# Sheet1.net
KiCad netlist of a schematic drawn in Altium Designer
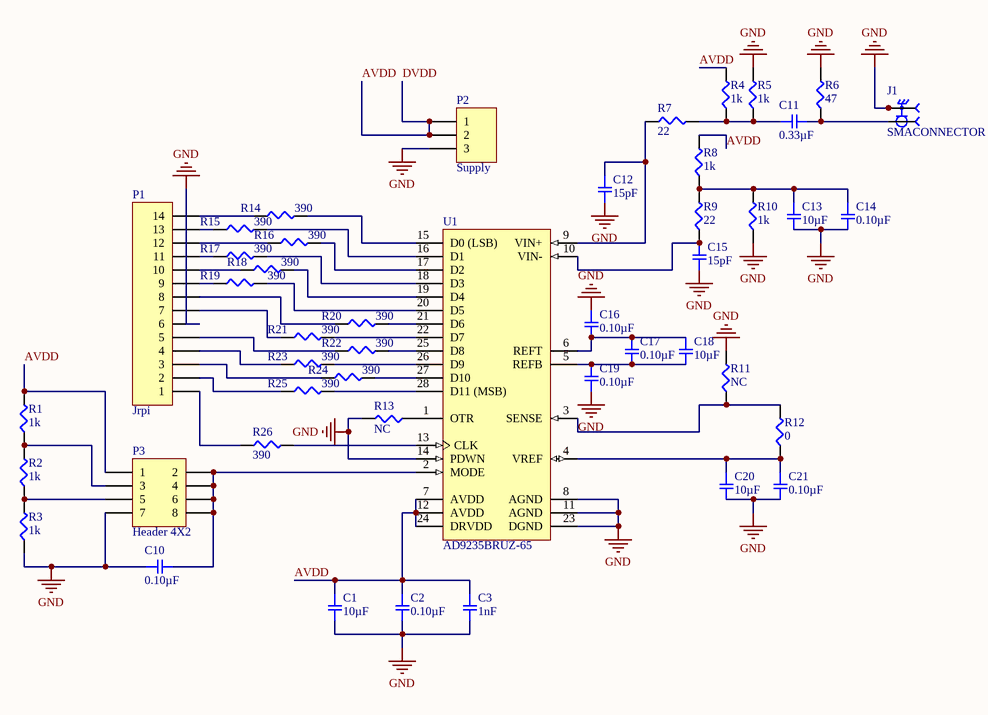
[diagram p0: Sheet1.SchDoc]

(export (version "E")
  (design (tool "Eeschema 10.0.6"))
  (components
    (comp (ref "C1")
      (value "10µF")
      (footprint "SMD-0603C")
      (description "CAP CER 10UF 6.3V X5R 0603")
      (fields
        (field (name "DIGI-KEY PART NUMBER") "490-10467-1-ND")
        (field (name "PART NUMBER") "GRM185R60J106ME15D")
      )
      (libsource (lib "capacitor_murata_0603") (part "GRM185R60J106ME15D"))
    )
    (comp (ref "C2")
      (value "0.10µF")
      (footprint "SMD-0603C")
      (description "CAP CER 0.1UF 16V X7R 0603")
      (fields
        (field (name "DIGI-KEY PART NUMBER") "490-5796-1-ND")
        (field (name "PART NUMBER") "GCJ188R71C104KA01D")
      )
      (libsource (lib "capacitor_murata_0603") (part "GCJ188R71C104KA01D"))
    )
    (comp (ref "C3")
      (value "1nF")
      (footprint "SMD-0603C")
      (description "CAP CER 1000PF 50V X7R 0603")
      (fields
        (field (name "DIGI-KEY PART NUMBER") "490-5768-1-ND")
        (field (name "PART NUMBER") "GCJ188R71H102KA01D")
      )
      (libsource (lib "capacitor_murata_0603") (part "GCJ188R71H102KA01D"))
    )
    (comp (ref "C10")
      (value "0.10µF")
      (footprint "SMD-0603C")
      (description "CAP CER 0.1UF 16V X7R 0603")
      (fields
        (field (name "DIGI-KEY PART NUMBER") "490-5796-1-ND")
        (field (name "PART NUMBER") "GCJ188R71C104KA01D")
      )
      (libsource (lib "capacitor_murata_0603") (part "GCJ188R71C104KA01D"))
    )
    (comp (ref "C11")
      (value "0.33µF")
      (footprint "SMD-0603C")
      (description "CAP CER 0.33UF 16V X7R 0603")
      (fields
        (field (name "DIGI-KEY PART NUMBER") "490-6050-1-ND")
        (field (name "PART NUMBER") "GCM188R71C334KA37D")
      )
      (libsource (lib "capacitor_murata_0603") (part "GCM188R71C334KA37D"))
    )
    (comp (ref "C12")
      (value "15pF")
      (footprint "SMD-0603C")
      (description "CAP CER 15PF 50V NP0 0603")
      (fields
        (field (name "DIGI-KEY PART NUMBER") "490-4957-1-ND")
        (field (name "PART NUMBER") "GCM1885C1H150JA16D")
      )
      (libsource (lib "capacitor_murata_0603") (part "GCM1885C1H150JA16D"))
    )
    (comp (ref "C13")
      (value "10µF")
      (footprint "SMD-0603C")
      (description "CAP CER 10UF 6.3V X5R 0603")
      (fields
        (field (name "DIGI-KEY PART NUMBER") "490-10467-1-ND")
        (field (name "PART NUMBER") "GRM185R60J106ME15D")
      )
      (libsource (lib "capacitor_murata_0603") (part "GRM185R60J106ME15D"))
    )
    (comp (ref "C14")
      (value "0.10µF")
      (footprint "SMD-0603C")
      (description "CAP CER 0.1UF 16V X7R 0603")
      (fields
        (field (name "DIGI-KEY PART NUMBER") "490-5796-1-ND")
        (field (name "PART NUMBER") "GCJ188R71C104KA01D")
      )
      (libsource (lib "capacitor_murata_0603") (part "GCJ188R71C104KA01D"))
    )
    (comp (ref "C15")
      (value "15pF")
      (footprint "SMD-0603C")
      (description "CAP CER 15PF 50V NP0 0603")
      (fields
        (field (name "DIGI-KEY PART NUMBER") "490-4957-1-ND")
        (field (name "PART NUMBER") "GCM1885C1H150JA16D")
      )
      (libsource (lib "capacitor_murata_0603") (part "GCM1885C1H150JA16D"))
    )
    (comp (ref "C16")
      (value "0.10µF")
      (footprint "SMD-0603C")
      (description "CAP CER 0.1UF 16V X7R 0603")
      (fields
        (field (name "DIGI-KEY PART NUMBER") "490-5796-1-ND")
        (field (name "PART NUMBER") "GCJ188R71C104KA01D")
      )
      (libsource (lib "capacitor_murata_0603") (part "GCJ188R71C104KA01D"))
    )
    (comp (ref "C17")
      (value "0.10µF")
      (footprint "SMD-0603C")
      (description "CAP CER 0.1UF 16V X7R 0603")
      (fields
        (field (name "DIGI-KEY PART NUMBER") "490-5796-1-ND")
        (field (name "PART NUMBER") "GCJ188R71C104KA01D")
      )
      (libsource (lib "capacitor_murata_0603") (part "GCJ188R71C104KA01D"))
    )
    (comp (ref "C18")
      (value "10µF")
      (footprint "SMD-0603C")
      (description "CAP CER 10UF 6.3V X5R 0603")
      (fields
        (field (name "DIGI-KEY PART NUMBER") "490-10467-1-ND")
        (field (name "PART NUMBER") "GRM185R60J106ME15D")
      )
      (libsource (lib "capacitor_murata_0603") (part "GRM185R60J106ME15D"))
    )
    (comp (ref "C19")
      (value "0.10µF")
      (footprint "SMD-0603C")
      (description "CAP CER 0.1UF 16V X7R 0603")
      (fields
        (field (name "DIGI-KEY PART NUMBER") "490-5796-1-ND")
        (field (name "PART NUMBER") "GCJ188R71C104KA01D")
      )
      (libsource (lib "capacitor_murata_0603") (part "GCJ188R71C104KA01D"))
    )
    (comp (ref "C20")
      (value "10µF")
      (footprint "SMD-0603C")
      (description "CAP CER 10UF 6.3V X5R 0603")
      (fields
        (field (name "DIGI-KEY PART NUMBER") "490-10467-1-ND")
        (field (name "PART NUMBER") "GRM185R60J106ME15D")
      )
      (libsource (lib "capacitor_murata_0603") (part "GRM185R60J106ME15D"))
    )
    (comp (ref "C21")
      (value "0.10µF")
      (footprint "SMD-0603C")
      (description "CAP CER 0.1UF 16V X7R 0603")
      (fields
        (field (name "DIGI-KEY PART NUMBER") "490-5796-1-ND")
        (field (name "PART NUMBER") "GCJ188R71C104KA01D")
      )
      (libsource (lib "capacitor_murata_0603") (part "GCJ188R71C104KA01D"))
    )
    (comp (ref "J1")
      (value "SMACONNECTOR")
      (footprint "LPRS_SMACONNECTOR")
      (description "SMA female RF coaxial connector for SMA male RF antennas.")
      (libsource (lib "SMACONNECTOR") (part "SMACONNECTOR"))
    )
    (comp (ref "P1")
      (value "Jrpi")
      (footprint "HDR1X14")
      (description "Header, 14-Pin")
      (fields (field (name "PUBLISHER") "Altium Limited"))
      (libsource (lib "Miscellaneous Connectors") (part "Header 14"))
    )
    (comp (ref "P2")
      (value "Supply")
      (footprint "HDR1X3")
      (description "Header, 3-Pin")
      (fields (field (name "PUBLISHER") "Altium Limited"))
      (libsource (lib "Miscellaneous Connectors") (part "Header 3"))
    )
    (comp (ref "P3")
      (value "Header 4X2")
      (footprint "HDR2X4")
      (description "Header, 4-Pin, Dual row")
      (fields (field (name "PUBLISHER") "Altium Limited"))
      (libsource (lib "Miscellaneous Connectors") (part "Header 4X2"))
    )
    (comp (ref "R1")
      (value "1k")
      (footprint "SMD-0603-RES")
      (description "RES SMD 1K OHM 1% 1/10W 0603")
      (fields
        (field (name "PART NUMBER") "ERJ-3EKF1001V")
        (field (name "DIGI-KEY PART NUMBER") "P1.00KHCT-ND")
      )
      (libsource (lib "Panasonic_ERJ_0603") (part "ERJ-3EKF1001V"))
    )
    (comp (ref "R2")
      (value "1k")
      (footprint "SMD-0603-RES")
      (description "RES SMD 1K OHM 1% 1/10W 0603")
      (fields
        (field (name "PART NUMBER") "ERJ-3EKF1001V")
        (field (name "DIGI-KEY PART NUMBER") "P1.00KHCT-ND")
      )
      (libsource (lib "Panasonic_ERJ_0603") (part "ERJ-3EKF1001V"))
    )
    (comp (ref "R3")
      (value "1k")
      (footprint "SMD-0603-RES")
      (description "RES SMD 1K OHM 1% 1/10W 0603")
      (fields
        (field (name "PART NUMBER") "ERJ-3EKF1001V")
        (field (name "DIGI-KEY PART NUMBER") "P1.00KHCT-ND")
      )
      (libsource (lib "Panasonic_ERJ_0603") (part "ERJ-3EKF1001V"))
    )
    (comp (ref "R4")
      (value "1k")
      (footprint "SMD-0603-RES")
      (description "RES SMD 1K OHM 1% 1/10W 0603")
      (fields
        (field (name "PART NUMBER") "ERJ-3EKF1001V")
        (field (name "DIGI-KEY PART NUMBER") "P1.00KHCT-ND")
      )
      (libsource (lib "Panasonic_ERJ_0603") (part "ERJ-3EKF1001V"))
    )
    (comp (ref "R5")
      (value "1k")
      (footprint "SMD-0603-RES")
      (description "RES SMD 1K OHM 1% 1/10W 0603")
      (fields
        (field (name "PART NUMBER") "ERJ-3EKF1001V")
        (field (name "DIGI-KEY PART NUMBER") "P1.00KHCT-ND")
      )
      (libsource (lib "Panasonic_ERJ_0603") (part "ERJ-3EKF1001V"))
    )
    (comp (ref "R6")
      (value "47")
      (footprint "SMD-0603-RES")
      (description "RES SMD 47 OHM 1% 1/4W 0603")
      (fields
        (field (name "PART NUMBER") "ERJ-PA3F47R0V")
        (field (name "DIGI-KEY PART NUMBER") "P47.00BYCT-ND")
      )
      (libsource (lib "Panasonic_ERJ_0603") (part "ERJ-PA3F47R0V"))
    )
    (comp (ref "R7")
      (value "22")
      (footprint "SMD-0603-RES")
      (description "RES SMD 22 OHM 5% 1/10W 0603")
      (fields (field (name "PART NUMBER") "ERJ-3GEYJ220V") (field (name "DIGI-KEY PART NUMBER") "P22GCT-ND"))
      (libsource (lib "Panasonic_ERJ_0603") (part "ERJ-3GEYJ220V"))
    )
    (comp (ref "R8")
      (value "1k")
      (footprint "SMD-0603-RES")
      (description "RES SMD 1K OHM 1% 1/10W 0603")
      (fields
        (field (name "PART NUMBER") "ERJ-3EKF1001V")
        (field (name "DIGI-KEY PART NUMBER") "P1.00KHCT-ND")
      )
      (libsource (lib "Panasonic_ERJ_0603") (part "ERJ-3EKF1001V"))
    )
    (comp (ref "R9")
      (value "22")
      (footprint "SMD-0603-RES")
      (description "RES SMD 22 OHM 5% 1/10W 0603")
      (fields (field (name "PART NUMBER") "ERJ-3GEYJ220V") (field (name "DIGI-KEY PART NUMBER") "P22GCT-ND"))
      (libsource (lib "Panasonic_ERJ_0603") (part "ERJ-3GEYJ220V"))
    )
    (comp (ref "R10")
      (value "1k")
      (footprint "SMD-0603-RES")
      (description "RES SMD 1K OHM 1% 1/10W 0603")
      (fields
        (field (name "PART NUMBER") "ERJ-3EKF1001V")
        (field (name "DIGI-KEY PART NUMBER") "P1.00KHCT-ND")
      )
      (libsource (lib "Panasonic_ERJ_0603") (part "ERJ-3EKF1001V"))
    )
    (comp (ref "R11")
      (value "NC")
      (footprint "SMD-0603-RES")
      (description "RES SMD 0.02 OHM 1% 1/3W 0603")
      (fields
        (field (name "PART NUMBER") "ERJ-3BWFR020V")
        (field (name "DIGI-KEY PART NUMBER") "P17461CT-ND")
      )
      (libsource (lib "Panasonic_ERJ_0603") (part "ERJ-3BWFR020V"))
    )
    (comp (ref "R12")
      (value "0")
      (footprint "SMD-0603-RES")
      (description "RES SMD 0.02 OHM 1% 1/3W 0603")
      (fields
        (field (name "PART NUMBER") "ERJ-3BWFR020V")
        (field (name "DIGI-KEY PART NUMBER") "P17461CT-ND")
      )
      (libsource (lib "Panasonic_ERJ_0603") (part "ERJ-3BWFR020V"))
    )
    (comp (ref "R13")
      (value "NC")
      (footprint "SMD-0603-RES")
      (description "RES SMD 0.02 OHM 1% 1/3W 0603")
      (fields
        (field (name "PART NUMBER") "ERJ-3BWFR020V")
        (field (name "DIGI-KEY PART NUMBER") "P17461CT-ND")
      )
      (libsource (lib "Panasonic_ERJ_0603") (part "ERJ-3BWFR020V"))
    )
    (comp (ref "R14")
      (value "390")
      (footprint "SMD-0603-RES")
      (description "RES SMD 390 OHM 1% 1/10W 0603")
      (fields (field (name "PART NUMBER") "ERJ-3EKF3900V") (field (name "DIGI-KEY PART NUMBER") "P390HCT-ND"))
      (libsource (lib "Panasonic_ERJ_0603") (part "ERJ-3EKF3900V"))
    )
    (comp (ref "R15")
      (value "390")
      (footprint "SMD-0603-RES")
      (description "RES SMD 390 OHM 1% 1/10W 0603")
      (fields (field (name "PART NUMBER") "ERJ-3EKF3900V") (field (name "DIGI-KEY PART NUMBER") "P390HCT-ND"))
      (libsource (lib "Panasonic_ERJ_0603") (part "ERJ-3EKF3900V"))
    )
    (comp (ref "R16")
      (value "390")
      (footprint "SMD-0603-RES")
      (description "RES SMD 390 OHM 1% 1/10W 0603")
      (fields (field (name "PART NUMBER") "ERJ-3EKF3900V") (field (name "DIGI-KEY PART NUMBER") "P390HCT-ND"))
      (libsource (lib "Panasonic_ERJ_0603") (part "ERJ-3EKF3900V"))
    )
    (comp (ref "R17")
      (value "390")
      (footprint "SMD-0603-RES")
      (description "RES SMD 390 OHM 1% 1/10W 0603")
      (fields (field (name "PART NUMBER") "ERJ-3EKF3900V") (field (name "DIGI-KEY PART NUMBER") "P390HCT-ND"))
      (libsource (lib "Panasonic_ERJ_0603") (part "ERJ-3EKF3900V"))
    )
    (comp (ref "R18")
      (value "390")
      (footprint "SMD-0603-RES")
      (description "RES SMD 390 OHM 1% 1/10W 0603")
      (fields (field (name "PART NUMBER") "ERJ-3EKF3900V") (field (name "DIGI-KEY PART NUMBER") "P390HCT-ND"))
      (libsource (lib "Panasonic_ERJ_0603") (part "ERJ-3EKF3900V"))
    )
    (comp (ref "R19")
      (value "390")
      (footprint "SMD-0603-RES")
      (description "RES SMD 390 OHM 1% 1/10W 0603")
      (fields (field (name "PART NUMBER") "ERJ-3EKF3900V") (field (name "DIGI-KEY PART NUMBER") "P390HCT-ND"))
      (libsource (lib "Panasonic_ERJ_0603") (part "ERJ-3EKF3900V"))
    )
    (comp (ref "R20")
      (value "390")
      (footprint "SMD-0603-RES")
      (description "RES SMD 390 OHM 1% 1/10W 0603")
      (fields (field (name "PART NUMBER") "ERJ-3EKF3900V") (field (name "DIGI-KEY PART NUMBER") "P390HCT-ND"))
      (libsource (lib "Panasonic_ERJ_0603") (part "ERJ-3EKF3900V"))
    )
    (comp (ref "R21")
      (value "390")
      (footprint "SMD-0603-RES")
      (description "RES SMD 390 OHM 1% 1/10W 0603")
      (fields (field (name "PART NUMBER") "ERJ-3EKF3900V") (field (name "DIGI-KEY PART NUMBER") "P390HCT-ND"))
      (libsource (lib "Panasonic_ERJ_0603") (part "ERJ-3EKF3900V"))
    )
    (comp (ref "R22")
      (value "390")
      (footprint "SMD-0603-RES")
      (description "RES SMD 390 OHM 1% 1/10W 0603")
      (fields (field (name "PART NUMBER") "ERJ-3EKF3900V") (field (name "DIGI-KEY PART NUMBER") "P390HCT-ND"))
      (libsource (lib "Panasonic_ERJ_0603") (part "ERJ-3EKF3900V"))
    )
    (comp (ref "R23")
      (value "390")
      (footprint "SMD-0603-RES")
      (description "RES SMD 390 OHM 1% 1/10W 0603")
      (fields (field (name "PART NUMBER") "ERJ-3EKF3900V") (field (name "DIGI-KEY PART NUMBER") "P390HCT-ND"))
      (libsource (lib "Panasonic_ERJ_0603") (part "ERJ-3EKF3900V"))
    )
    (comp (ref "R24")
      (value "390")
      (footprint "SMD-0603-RES")
      (description "RES SMD 390 OHM 1% 1/10W 0603")
      (fields (field (name "PART NUMBER") "ERJ-3EKF3900V") (field (name "DIGI-KEY PART NUMBER") "P390HCT-ND"))
      (libsource (lib "Panasonic_ERJ_0603") (part "ERJ-3EKF3900V"))
    )
    (comp (ref "R25")
      (value "390")
      (footprint "SMD-0603-RES")
      (description "RES SMD 390 OHM 1% 1/10W 0603")
      (fields (field (name "PART NUMBER") "ERJ-3EKF3900V") (field (name "DIGI-KEY PART NUMBER") "P390HCT-ND"))
      (libsource (lib "Panasonic_ERJ_0603") (part "ERJ-3EKF3900V"))
    )
    (comp (ref "R26")
      (value "390")
      (footprint "SMD-0603-RES")
      (description "RES SMD 390 OHM 1% 1/10W 0603")
      (fields (field (name "PART NUMBER") "ERJ-3EKF3900V") (field (name "DIGI-KEY PART NUMBER") "P390HCT-ND"))
      (libsource (lib "Panasonic_ERJ_0603") (part "ERJ-3EKF3900V"))
    )
    (comp (ref "U1")
      (value "AD9235BRUZ-65")
      (footprint "RU-28_M")
      (fields (field (name "GENERIC PART NUMBER") "AD9235-65") (field (name "MANUFACTURER") "Analog Devices"))
      (libsource (lib "Altium Content Vault") (part "ADI-AD9235-65-RU-28"))
    )
  )
  (nets
    (net (code "1") (name "/AVDD") (class "Default")
      (node (ref "C1") (pin "1") (pinfunction "1_1") (pintype "passive"))
      (node (ref "C2") (pin "1") (pinfunction "1_1") (pintype "passive"))
      (node (ref "C3") (pin "1") (pinfunction "1_1") (pintype "passive"))
      (node (ref "P2") (pin "1") (pinfunction "1_1") (pintype "passive"))
      (node (ref "P2") (pin "2") (pinfunction "2_2") (pintype "passive"))
      (node (ref "P3") (pin "1") (pinfunction "1_1") (pintype "passive"))
      (node (ref "R1") (pin "2") (pinfunction "2_2") (pintype "passive"))
      (node (ref "R4") (pin "2") (pinfunction "2_2") (pintype "passive"))
      (node (ref "R8") (pin "2") (pinfunction "2_2") (pintype "passive"))
      (node (ref "U1") (pin "12") (pinfunction "AVDD_12") (pintype "power_in"))
      (node (ref "U1") (pin "24") (pinfunction "DRVDD_24") (pintype "power_in"))
      (node (ref "U1") (pin "7") (pinfunction "AVDD_7") (pintype "power_in"))
    )
    (net (code "2") (name "GND") (class "Default")
      (node (ref "C1") (pin "2") (pinfunction "2_2") (pintype "passive"))
      (node (ref "C10") (pin "1") (pinfunction "1_1") (pintype "passive"))
      (node (ref "C12") (pin "2") (pinfunction "2_2") (pintype "passive"))
      (node (ref "C13") (pin "2") (pinfunction "2_2") (pintype "passive"))
      (node (ref "C14") (pin "2") (pinfunction "2_2") (pintype "passive"))
      (node (ref "C15") (pin "2") (pinfunction "2_2") (pintype "passive"))
      (node (ref "C16") (pin "1") (pinfunction "1_1") (pintype "passive"))
      (node (ref "C19") (pin "2") (pinfunction "2_2") (pintype "passive"))
      (node (ref "C2") (pin "2") (pinfunction "2_2") (pintype "passive"))
      (node (ref "C20") (pin "2") (pinfunction "2_2") (pintype "passive"))
      (node (ref "C21") (pin "2") (pinfunction "2_2") (pintype "passive"))
      (node (ref "C3") (pin "2") (pinfunction "2_2") (pintype "passive"))
      (node (ref "J1") (pin "2") (pinfunction "2_2") (pintype "passive"))
      (node (ref "J1") (pin "3") (pinfunction "2_3") (pintype "passive"))
      (node (ref "J1") (pin "4") (pinfunction "2_4") (pintype "passive"))
      (node (ref "J1") (pin "5") (pinfunction "2_5") (pintype "passive"))
      (node (ref "P1") (pin "6") (pinfunction "6_6") (pintype "passive"))
      (node (ref "P2") (pin "3") (pinfunction "3_3") (pintype "passive"))
      (node (ref "P3") (pin "7") (pinfunction "7_7") (pintype "passive"))
      (node (ref "R10") (pin "1") (pinfunction "1_1") (pintype "passive"))
      (node (ref "R11") (pin "2") (pinfunction "2_2") (pintype "passive"))
      (node (ref "R13") (pin "2") (pinfunction "2_2") (pintype "passive"))
      (node (ref "R3") (pin "1") (pinfunction "1_1") (pintype "passive"))
      (node (ref "R5") (pin "2") (pinfunction "2_2") (pintype "passive"))
      (node (ref "R6") (pin "2") (pinfunction "2_2") (pintype "passive"))
      (node (ref "U1") (pin "11") (pinfunction "AGND_11") (pintype "power_in"))
      (node (ref "U1") (pin "14") (pinfunction "PDWN_14") (pintype "input"))
      (node (ref "U1") (pin "23") (pinfunction "DGND_23") (pintype "power_in"))
      (node (ref "U1") (pin "8") (pinfunction "AGND_8") (pintype "power_in"))
    )
    (net (code "3") (name "Net-(C11-Pad1)") (class "Default")
      (node (ref "C11") (pin "1") (pinfunction "1_1") (pintype "passive"))
      (node (ref "R4") (pin "1") (pinfunction "1_1") (pintype "passive"))
      (node (ref "R5") (pin "1") (pinfunction "1_1") (pintype "passive"))
      (node (ref "R7") (pin "2") (pinfunction "2_2") (pintype "passive"))
    )
    (net (code "4") (name "Net-(C11-Pad2)") (class "Default")
      (node (ref "C11") (pin "2") (pinfunction "2_2") (pintype "passive"))
      (node (ref "J1") (pin "1") (pinfunction "1_1") (pintype "passive"))
      (node (ref "R6") (pin "1") (pinfunction "1_1") (pintype "passive"))
    )
    (net (code "5") (name "Net-(C13-Pad1)") (class "Default")
      (node (ref "C13") (pin "1") (pinfunction "1_1") (pintype "passive"))
      (node (ref "C14") (pin "1") (pinfunction "1_1") (pintype "passive"))
      (node (ref "R10") (pin "2") (pinfunction "2_2") (pintype "passive"))
      (node (ref "R8") (pin "1") (pinfunction "1_1") (pintype "passive"))
      (node (ref "R9") (pin "2") (pinfunction "2_2") (pintype "passive"))
    )
    (net (code "6") (name "Net-(P1-Pad1)") (class "Default")
      (node (ref "P1") (pin "1") (pinfunction "1_1") (pintype "passive"))
      (node (ref "R26") (pin "1") (pinfunction "1_1") (pintype "passive"))
    )
    (net (code "7") (name "Net-(P1-Pad2)") (class "Default")
      (node (ref "P1") (pin "2") (pinfunction "2_2") (pintype "passive"))
      (node (ref "R25") (pin "1") (pinfunction "1_1") (pintype "passive"))
    )
    (net (code "8") (name "Net-(P1-Pad3)") (class "Default")
      (node (ref "P1") (pin "3") (pinfunction "3_3") (pintype "passive"))
      (node (ref "R24") (pin "1") (pinfunction "1_1") (pintype "passive"))
    )
    (net (code "9") (name "Net-(P1-Pad4)") (class "Default")
      (node (ref "P1") (pin "4") (pinfunction "4_4") (pintype "passive"))
      (node (ref "R23") (pin "1") (pinfunction "1_1") (pintype "passive"))
    )
    (net (code "10") (name "Net-(P1-Pad5)") (class "Default")
      (node (ref "P1") (pin "5") (pinfunction "5_5") (pintype "passive"))
      (node (ref "R22") (pin "1") (pinfunction "1_1") (pintype "passive"))
    )
    (net (code "11") (name "Net-(P1-Pad7)") (class "Default")
      (node (ref "P1") (pin "7") (pinfunction "7_7") (pintype "passive"))
      (node (ref "R21") (pin "1") (pinfunction "1_1") (pintype "passive"))
    )
    (net (code "12") (name "Net-(P1-Pad8)") (class "Default")
      (node (ref "P1") (pin "8") (pinfunction "8_8") (pintype "passive"))
      (node (ref "R20") (pin "1") (pinfunction "1_1") (pintype "passive"))
    )
    (net (code "13") (name "Net-(P1-Pad9)") (class "Default")
      (node (ref "P1") (pin "9") (pinfunction "9_9") (pintype "passive"))
      (node (ref "R19") (pin "1") (pinfunction "1_1") (pintype "passive"))
    )
    (net (code "14") (name "Net-(P1-Pad10)") (class "Default")
      (node (ref "P1") (pin "10") (pinfunction "10_10") (pintype "passive"))
      (node (ref "R18") (pin "1") (pinfunction "1_1") (pintype "passive"))
    )
    (net (code "15") (name "Net-(P1-Pad11)") (class "Default")
      (node (ref "P1") (pin "11") (pinfunction "11_11") (pintype "passive"))
      (node (ref "R17") (pin "1") (pinfunction "1_1") (pintype "passive"))
    )
    (net (code "16") (name "Net-(P1-Pad12)") (class "Default")
      (node (ref "P1") (pin "12") (pinfunction "12_12") (pintype "passive"))
      (node (ref "R16") (pin "1") (pinfunction "1_1") (pintype "passive"))
    )
    (net (code "17") (name "Net-(P1-Pad13)") (class "Default")
      (node (ref "P1") (pin "13") (pinfunction "13_13") (pintype "passive"))
      (node (ref "R15") (pin "1") (pinfunction "1_1") (pintype "passive"))
    )
    (net (code "18") (name "Net-(P1-Pad14)") (class "Default")
      (node (ref "P1") (pin "14") (pinfunction "14_14") (pintype "passive"))
      (node (ref "R14") (pin "1") (pinfunction "1_1") (pintype "passive"))
    )
    (net (code "19") (name "Net-(P3-Pad3)") (class "Default")
      (node (ref "P3") (pin "3") (pinfunction "3_3") (pintype "passive"))
      (node (ref "R1") (pin "1") (pinfunction "1_1") (pintype "passive"))
      (node (ref "R2") (pin "2") (pinfunction "2_2") (pintype "passive"))
    )
    (net (code "20") (name "Net-(P3-Pad5)") (class "Default")
      (node (ref "P3") (pin "5") (pinfunction "5_5") (pintype "passive"))
      (node (ref "R2") (pin "1") (pinfunction "1_1") (pintype "passive"))
      (node (ref "R3") (pin "2") (pinfunction "2_2") (pintype "passive"))
    )
    (net (code "21") (name "Net-(U1-CLK)") (class "Default")
      (node (ref "R26") (pin "2") (pinfunction "2_2") (pintype "passive"))
      (node (ref "U1") (pin "13") (pinfunction "CLK_13") (pintype "input"))
    )
    (net (code "22") (name "Net-(U1-D0_(LSB))") (class "Default")
      (node (ref "R14") (pin "2") (pinfunction "2_2") (pintype "passive"))
      (node (ref "U1") (pin "15") (pinfunction "D0_(LSB)_15") (pintype "tri_state"))
    )
    (net (code "23") (name "Net-(U1-D1)") (class "Default")
      (node (ref "R15") (pin "2") (pinfunction "2_2") (pintype "passive"))
      (node (ref "U1") (pin "16") (pinfunction "D1_16") (pintype "tri_state"))
    )
    (net (code "24") (name "Net-(U1-D2)") (class "Default")
      (node (ref "R16") (pin "2") (pinfunction "2_2") (pintype "passive"))
      (node (ref "U1") (pin "17") (pinfunction "D2_17") (pintype "tri_state"))
    )
    (net (code "25") (name "Net-(U1-D3)") (class "Default")
      (node (ref "R17") (pin "2") (pinfunction "2_2") (pintype "passive"))
      (node (ref "U1") (pin "18") (pinfunction "D3_18") (pintype "tri_state"))
    )
    (net (code "26") (name "Net-(U1-D4)") (class "Default")
      (node (ref "R18") (pin "2") (pinfunction "2_2") (pintype "passive"))
      (node (ref "U1") (pin "19") (pinfunction "D4_19") (pintype "tri_state"))
    )
    (net (code "27") (name "Net-(U1-D5)") (class "Default")
      (node (ref "R19") (pin "2") (pinfunction "2_2") (pintype "passive"))
      (node (ref "U1") (pin "20") (pinfunction "D5_20") (pintype "tri_state"))
    )
    (net (code "28") (name "Net-(U1-D6)") (class "Default")
      (node (ref "R20") (pin "2") (pinfunction "2_2") (pintype "passive"))
      (node (ref "U1") (pin "21") (pinfunction "D6_21") (pintype "tri_state"))
    )
    (net (code "29") (name "Net-(U1-D7)") (class "Default")
      (node (ref "R21") (pin "2") (pinfunction "2_2") (pintype "passive"))
      (node (ref "U1") (pin "22") (pinfunction "D7_22") (pintype "tri_state"))
    )
    (net (code "30") (name "Net-(U1-D8)") (class "Default")
      (node (ref "R22") (pin "2") (pinfunction "2_2") (pintype "passive"))
      (node (ref "U1") (pin "25") (pinfunction "D8_25") (pintype "tri_state"))
    )
    (net (code "31") (name "Net-(U1-D9)") (class "Default")
      (node (ref "R23") (pin "2") (pinfunction "2_2") (pintype "passive"))
      (node (ref "U1") (pin "26") (pinfunction "D9_26") (pintype "tri_state"))
    )
    (net (code "32") (name "Net-(U1-D10)") (class "Default")
      (node (ref "R24") (pin "2") (pinfunction "2_2") (pintype "passive"))
      (node (ref "U1") (pin "27") (pinfunction "D10_27") (pintype "tri_state"))
    )
    (net (code "33") (name "Net-(U1-D11_(MSB))") (class "Default")
      (node (ref "R25") (pin "2") (pinfunction "2_2") (pintype "passive"))
      (node (ref "U1") (pin "28") (pinfunction "D11_(MSB)_28") (pintype "tri_state"))
    )
    (net (code "34") (name "Net-(U1-MODE)") (class "Default")
      (node (ref "C10") (pin "2") (pinfunction "2_2") (pintype "passive"))
      (node (ref "P3") (pin "2") (pinfunction "2_2") (pintype "passive"))
      (node (ref "P3") (pin "4") (pinfunction "4_4") (pintype "passive"))
      (node (ref "P3") (pin "6") (pinfunction "6_6") (pintype "passive"))
      (node (ref "P3") (pin "8") (pinfunction "8_8") (pintype "passive"))
      (node (ref "U1") (pin "2") (pinfunction "MODE_2") (pintype "input"))
    )
    (net (code "35") (name "Net-(U1-OTR)") (class "Default")
      (node (ref "R13") (pin "1") (pinfunction "1_1") (pintype "passive"))
      (node (ref "U1") (pin "1") (pinfunction "OTR_1") (pintype "tri_state"))
    )
    (net (code "36") (name "Net-(U1-REFB)") (class "Default")
      (node (ref "C17") (pin "2") (pinfunction "2_2") (pintype "passive"))
      (node (ref "C18") (pin "2") (pinfunction "2_2") (pintype "passive"))
      (node (ref "C19") (pin "1") (pinfunction "1_1") (pintype "passive"))
      (node (ref "U1") (pin "5") (pinfunction "REFB_5") (pintype "passive"))
    )
    (net (code "37") (name "Net-(U1-REFT)") (class "Default")
      (node (ref "C16") (pin "2") (pinfunction "2_2") (pintype "passive"))
      (node (ref "C17") (pin "1") (pinfunction "1_1") (pintype "passive"))
      (node (ref "C18") (pin "1") (pinfunction "1_1") (pintype "passive"))
      (node (ref "U1") (pin "6") (pinfunction "REFT_6") (pintype "passive"))
    )
    (net (code "38") (name "Net-(U1-SENSE)") (class "Default")
      (node (ref "R11") (pin "1") (pinfunction "1_1") (pintype "passive"))
      (node (ref "R12") (pin "2") (pinfunction "2_2") (pintype "passive"))
      (node (ref "U1") (pin "3") (pinfunction "SENSE_3") (pintype "input"))
    )
    (net (code "39") (name "Net-(U1-VIN+)") (class "Default")
      (node (ref "C12") (pin "1") (pinfunction "1_1") (pintype "passive"))
      (node (ref "R7") (pin "1") (pinfunction "1_1") (pintype "passive"))
      (node (ref "U1") (pin "9") (pinfunction "VIN+_9") (pintype "input"))
    )
    (net (code "40") (name "Net-(U1-VIN-)") (class "Default")
      (node (ref "C15") (pin "1") (pinfunction "1_1") (pintype "passive"))
      (node (ref "R9") (pin "1") (pinfunction "1_1") (pintype "passive"))
      (node (ref "U1") (pin "10") (pinfunction "VIN-_10") (pintype "input"))
    )
    (net (code "41") (name "Net-(U1-VREF)") (class "Default")
      (node (ref "C20") (pin "1") (pinfunction "1_1") (pintype "passive"))
      (node (ref "C21") (pin "1") (pinfunction "1_1") (pintype "passive"))
      (node (ref "R12") (pin "1") (pinfunction "1_1") (pintype "passive"))
      (node (ref "U1") (pin "4") (pinfunction "VREF_4") (pintype "bidirectional"))
    )
  )
)
